# MCU.net
KiCad netlist of a schematic drawn in Altium Designer
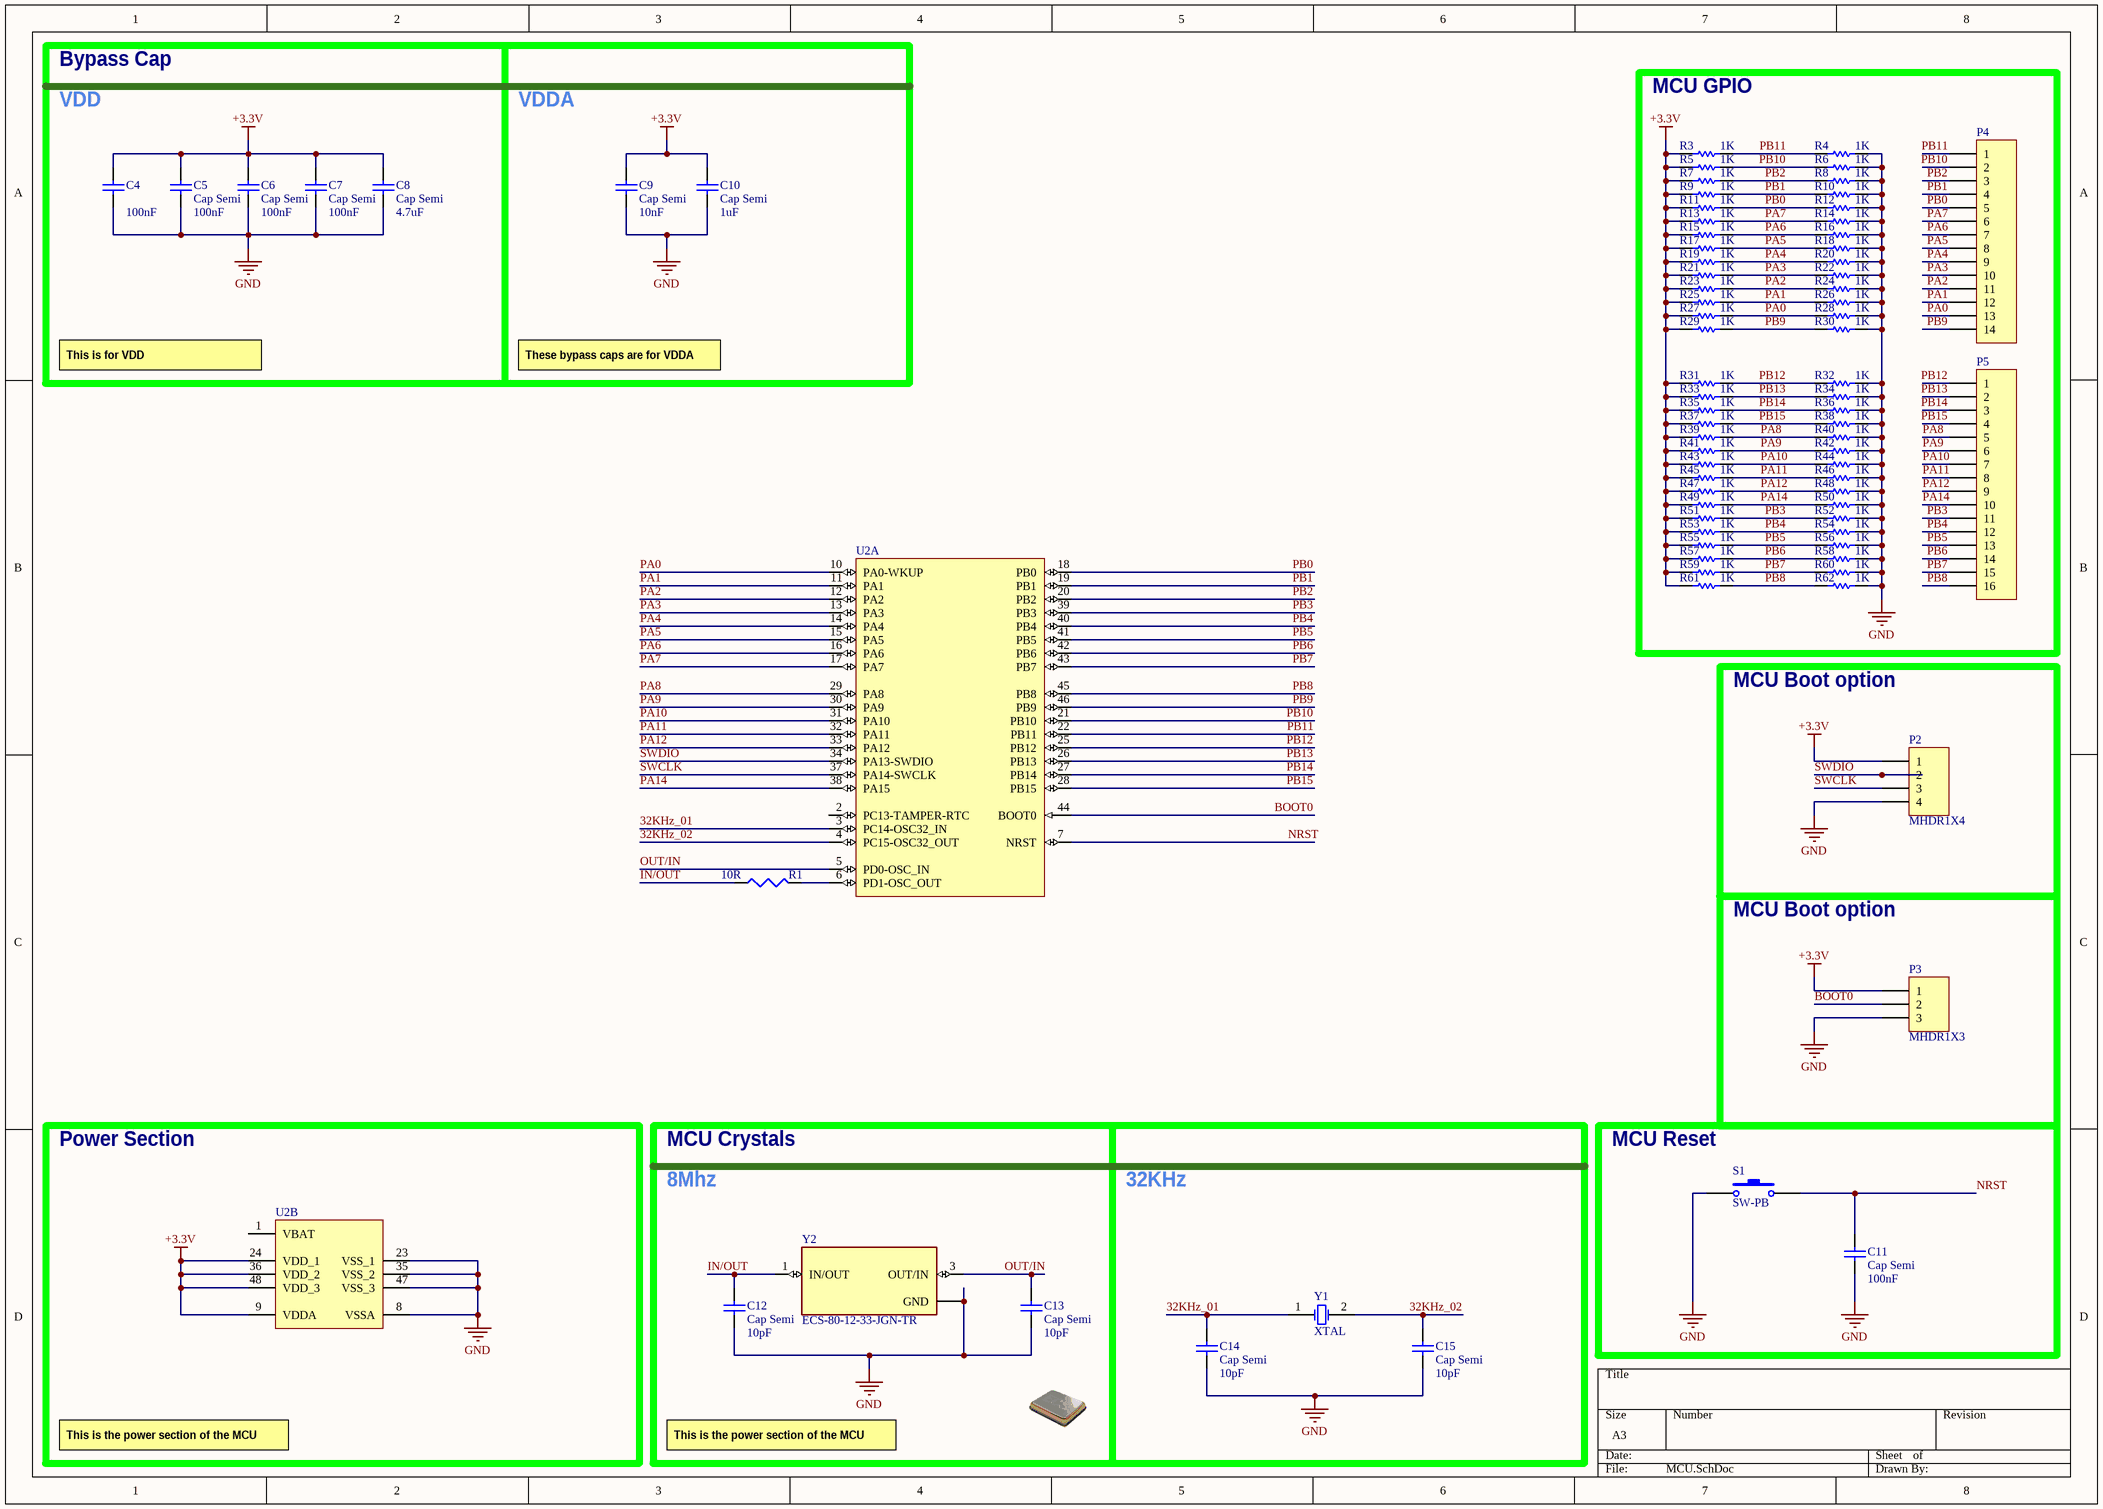
[diagram p0: MCU.SchDoc]

(export (version "E")
  (design (tool "Eeschema 10.0.6"))
  (components
    (comp (ref "C4")
      (value "100nF")
      (footprint "1608[0603]")
      (description "Capacitor (Semiconductor SIM Model)")
      (fields (field (name "PUBLISHER") "Altium Limited"))
      (libsource (lib "smartmcu") (part "Cap Semi"))
    )
    (comp (ref "C5")
      (value "Cap Semi")
      (footprint "1608[0603]")
      (description "Capacitor (Semiconductor SIM Model)")
      (fields (field (name "ALTIUM_VALUE") "100nF") (field (name "PUBLISHER") "Altium Limited"))
      (libsource (lib "Miscellaneous Devices") (part "Cap Semi"))
    )
    (comp (ref "C6")
      (value "Cap Semi")
      (footprint "1608[0603]")
      (description "Capacitor (Semiconductor SIM Model)")
      (fields (field (name "ALTIUM_VALUE") "100nF") (field (name "PUBLISHER") "Altium Limited"))
      (libsource (lib "Miscellaneous Devices") (part "Cap Semi"))
    )
    (comp (ref "C7")
      (value "Cap Semi")
      (footprint "1608[0603]")
      (description "Capacitor (Semiconductor SIM Model)")
      (fields (field (name "ALTIUM_VALUE") "100nF") (field (name "PUBLISHER") "Altium Limited"))
      (libsource (lib "Miscellaneous Devices") (part "Cap Semi"))
    )
    (comp (ref "C8")
      (value "Cap Semi")
      (footprint "1608[0603]")
      (description "Capacitor (Semiconductor SIM Model)")
      (fields (field (name "ALTIUM_VALUE") "4.7uF") (field (name "PUBLISHER") "Altium Limited"))
      (libsource (lib "Miscellaneous Devices") (part "Cap Semi"))
    )
    (comp (ref "C9")
      (value "Cap Semi")
      (footprint "1608[0603]")
      (description "Capacitor (Semiconductor SIM Model)")
      (fields (field (name "ALTIUM_VALUE") "10nF") (field (name "PUBLISHER") "Altium Limited"))
      (libsource (lib "Miscellaneous Devices") (part "Cap Semi"))
    )
    (comp (ref "C10")
      (value "Cap Semi")
      (footprint "1608[0603]")
      (description "Capacitor (Semiconductor SIM Model)")
      (fields (field (name "ALTIUM_VALUE") "1uF") (field (name "PUBLISHER") "Altium Limited"))
      (libsource (lib "Miscellaneous Devices") (part "Cap Semi"))
    )
    (comp (ref "C11")
      (value "Cap Semi")
      (footprint "1608[0603]")
      (description "Capacitor (Semiconductor SIM Model)")
      (fields (field (name "ALTIUM_VALUE") "100nF") (field (name "PUBLISHER") "Altium Limited"))
      (libsource (lib "Miscellaneous Devices") (part "Cap Semi"))
    )
    (comp (ref "C12")
      (value "Cap Semi")
      (footprint "0402")
      (description "Capacitor (Semiconductor SIM Model)")
      (fields (field (name "ALTIUM_VALUE") "10pF") (field (name "PUBLISHER") "Altium Limited"))
      (libsource (lib "Miscellaneous Devices") (part "Cap Semi"))
    )
    (comp (ref "C13")
      (value "Cap Semi")
      (footprint "0402")
      (description "Capacitor (Semiconductor SIM Model)")
      (fields (field (name "ALTIUM_VALUE") "10pF") (field (name "PUBLISHER") "Altium Limited"))
      (libsource (lib "Miscellaneous Devices") (part "Cap Semi"))
    )
    (comp (ref "C14")
      (value "Cap Semi")
      (footprint "0402")
      (description "Capacitor (Semiconductor SIM Model)")
      (fields (field (name "ALTIUM_VALUE") "10pF") (field (name "PUBLISHER") "Altium Limited"))
      (libsource (lib "Miscellaneous Devices") (part "Cap Semi"))
    )
    (comp (ref "C15")
      (value "Cap Semi")
      (footprint "0402")
      (description "Capacitor (Semiconductor SIM Model)")
      (fields (field (name "ALTIUM_VALUE") "10pF") (field (name "PUBLISHER") "Altium Limited"))
      (libsource (lib "Miscellaneous Devices") (part "Cap Semi"))
    )
    (comp (ref "P2")
      (value "MHDR1X4")
      (footprint "MHDR1X4")
      (description "Header, 4-Pin")
      (fields (field (name "PUBLISHER") "Altium Limited"))
      (libsource (lib "Miscellaneous Connectors") (part "MHDR1X4"))
    )
    (comp (ref "P3")
      (value "MHDR1X3")
      (footprint "MHDR1X3")
      (description "Header, 3-Pin")
      (fields (field (name "PUBLISHER") "Altium Limited"))
      (libsource (lib "Miscellaneous Connectors") (part "MHDR1X3"))
    )
    (comp (ref "P4")
      (value "Header 14")
      (footprint "MY_FE14")
      (description "Header, 14-Pin")
      (fields (field (name "ASID PART NUMBER") "Header 14-AS"))
      (libsource (lib "Mylib+Rev+4") (part "Header 14"))
    )
    (comp (ref "P5")
      (value "Header 16")
      (footprint "MY_FE16")
      (description "Header, 16-Pin")
      (fields (field (name "ASID PART NUMBER") "Header 16-AS"))
      (libsource (lib "Mylib+Rev+4") (part "Header 16"))
    )
    (comp (ref "R1")
      (value "10R")
      (footprint "J1-0603")
      (description "Resistor")
      (fields (field (name "Comment") "Res3") (field (name "PUBLISHER") "Altium Limited"))
      (libsource (lib "Miscellaneous Devices") (part "Res3"))
    )
    (comp (ref "R3")
      (value "1K")
      (footprint "MY_0603")
      (description "Standard resistor")
      (fields (field (name "ASID PART NUMBER") "Res-AS"))
      (libsource (lib "Mylib+Rev+4") (part "Res"))
    )
    (comp (ref "R4")
      (value "1K")
      (footprint "MY_0603")
      (description "Standard resistor")
      (fields (field (name "ASID PART NUMBER") "Res-AS"))
      (libsource (lib "Mylib+Rev+4") (part "Res"))
    )
    (comp (ref "R5")
      (value "1K")
      (footprint "MY_0603")
      (description "Standard resistor")
      (fields (field (name "ASID PART NUMBER") "Res-AS"))
      (libsource (lib "Mylib+Rev+4") (part "Res"))
    )
    (comp (ref "R6")
      (value "1K")
      (footprint "MY_0603")
      (description "Standard resistor")
      (fields (field (name "ASID PART NUMBER") "Res-AS"))
      (libsource (lib "Mylib+Rev+4") (part "Res"))
    )
    (comp (ref "R7")
      (value "1K")
      (footprint "MY_0603")
      (description "Standard resistor")
      (fields (field (name "ASID PART NUMBER") "Res-AS"))
      (libsource (lib "Mylib+Rev+4") (part "Res"))
    )
    (comp (ref "R8")
      (value "1K")
      (footprint "MY_0603")
      (description "Standard resistor")
      (fields (field (name "ASID PART NUMBER") "Res-AS"))
      (libsource (lib "Mylib+Rev+4") (part "Res"))
    )
    (comp (ref "R9")
      (value "1K")
      (footprint "MY_0603")
      (description "Standard resistor")
      (fields (field (name "ASID PART NUMBER") "Res-AS"))
      (libsource (lib "Mylib+Rev+4") (part "Res"))
    )
    (comp (ref "R10")
      (value "1K")
      (footprint "MY_0603")
      (description "Standard resistor")
      (fields (field (name "ASID PART NUMBER") "Res-AS"))
      (libsource (lib "Mylib+Rev+4") (part "Res"))
    )
    (comp (ref "R11")
      (value "1K")
      (footprint "MY_0603")
      (description "Standard resistor")
      (fields (field (name "ASID PART NUMBER") "Res-AS"))
      (libsource (lib "Mylib+Rev+4") (part "Res"))
    )
    (comp (ref "R12")
      (value "1K")
      (footprint "MY_0603")
      (description "Standard resistor")
      (fields (field (name "ASID PART NUMBER") "Res-AS"))
      (libsource (lib "Mylib+Rev+4") (part "Res"))
    )
    (comp (ref "R13")
      (value "1K")
      (footprint "MY_0603")
      (description "Standard resistor")
      (fields (field (name "ASID PART NUMBER") "Res-AS"))
      (libsource (lib "Mylib+Rev+4") (part "Res"))
    )
    (comp (ref "R14")
      (value "1K")
      (footprint "MY_0603")
      (description "Standard resistor")
      (fields (field (name "ASID PART NUMBER") "Res-AS"))
      (libsource (lib "Mylib+Rev+4") (part "Res"))
    )
    (comp (ref "R15")
      (value "1K")
      (footprint "MY_0603")
      (description "Standard resistor")
      (fields (field (name "ASID PART NUMBER") "Res-AS"))
      (libsource (lib "Mylib+Rev+4") (part "Res"))
    )
    (comp (ref "R16")
      (value "1K")
      (footprint "MY_0603")
      (description "Standard resistor")
      (fields (field (name "ASID PART NUMBER") "Res-AS"))
      (libsource (lib "Mylib+Rev+4") (part "Res"))
    )
    (comp (ref "R17")
      (value "1K")
      (footprint "MY_0603")
      (description "Standard resistor")
      (fields (field (name "ASID PART NUMBER") "Res-AS"))
      (libsource (lib "Mylib+Rev+4") (part "Res"))
    )
    (comp (ref "R18")
      (value "1K")
      (footprint "MY_0603")
      (description "Standard resistor")
      (fields (field (name "ASID PART NUMBER") "Res-AS"))
      (libsource (lib "Mylib+Rev+4") (part "Res"))
    )
    (comp (ref "R19")
      (value "1K")
      (footprint "MY_0603")
      (description "Standard resistor")
      (fields (field (name "ASID PART NUMBER") "Res-AS"))
      (libsource (lib "Mylib+Rev+4") (part "Res"))
    )
    (comp (ref "R20")
      (value "1K")
      (footprint "MY_0603")
      (description "Standard resistor")
      (fields (field (name "ASID PART NUMBER") "Res-AS"))
      (libsource (lib "Mylib+Rev+4") (part "Res"))
    )
    (comp (ref "R21")
      (value "1K")
      (footprint "MY_0603")
      (description "Standard resistor")
      (fields (field (name "ASID PART NUMBER") "Res-AS"))
      (libsource (lib "Mylib+Rev+4") (part "Res"))
    )
    (comp (ref "R22")
      (value "1K")
      (footprint "MY_0603")
      (description "Standard resistor")
      (fields (field (name "ASID PART NUMBER") "Res-AS"))
      (libsource (lib "Mylib+Rev+4") (part "Res"))
    )
    (comp (ref "R23")
      (value "1K")
      (footprint "MY_0603")
      (description "Standard resistor")
      (fields (field (name "ASID PART NUMBER") "Res-AS"))
      (libsource (lib "Mylib+Rev+4") (part "Res"))
    )
    (comp (ref "R24")
      (value "1K")
      (footprint "MY_0603")
      (description "Standard resistor")
      (fields (field (name "ASID PART NUMBER") "Res-AS"))
      (libsource (lib "Mylib+Rev+4") (part "Res"))
    )
    (comp (ref "R25")
      (value "1K")
      (footprint "MY_0603")
      (description "Standard resistor")
      (fields (field (name "ASID PART NUMBER") "Res-AS"))
      (libsource (lib "Mylib+Rev+4") (part "Res"))
    )
    (comp (ref "R26")
      (value "1K")
      (footprint "MY_0603")
      (description "Standard resistor")
      (fields (field (name "ASID PART NUMBER") "Res-AS"))
      (libsource (lib "Mylib+Rev+4") (part "Res"))
    )
    (comp (ref "R27")
      (value "1K")
      (footprint "MY_0603")
      (description "Standard resistor")
      (fields (field (name "ASID PART NUMBER") "Res-AS"))
      (libsource (lib "Mylib+Rev+4") (part "Res"))
    )
    (comp (ref "R28")
      (value "1K")
      (footprint "MY_0603")
      (description "Standard resistor")
      (fields (field (name "ASID PART NUMBER") "Res-AS"))
      (libsource (lib "Mylib+Rev+4") (part "Res"))
    )
    (comp (ref "R29")
      (value "1K")
      (footprint "MY_0603")
      (description "Standard resistor")
      (fields (field (name "ASID PART NUMBER") "Res-AS"))
      (libsource (lib "Mylib+Rev+4") (part "Res"))
    )
    (comp (ref "R30")
      (value "1K")
      (footprint "MY_0603")
      (description "Standard resistor")
      (fields (field (name "ASID PART NUMBER") "Res-AS"))
      (libsource (lib "Mylib+Rev+4") (part "Res"))
    )
    (comp (ref "R31")
      (value "1K")
      (footprint "MY_0603")
      (description "Standard resistor")
      (fields (field (name "ASID PART NUMBER") "Res-AS"))
      (libsource (lib "Mylib+Rev+4") (part "Res"))
    )
    (comp (ref "R32")
      (value "1K")
      (footprint "MY_0603")
      (description "Standard resistor")
      (fields (field (name "ASID PART NUMBER") "Res-AS"))
      (libsource (lib "Mylib+Rev+4") (part "Res"))
    )
    (comp (ref "R33")
      (value "1K")
      (footprint "MY_0603")
      (description "Standard resistor")
      (fields (field (name "ASID PART NUMBER") "Res-AS"))
      (libsource (lib "Mylib+Rev+4") (part "Res"))
    )
    (comp (ref "R34")
      (value "1K")
      (footprint "MY_0603")
      (description "Standard resistor")
      (fields (field (name "ASID PART NUMBER") "Res-AS"))
      (libsource (lib "Mylib+Rev+4") (part "Res"))
    )
    (comp (ref "R35")
      (value "1K")
      (footprint "MY_0603")
      (description "Standard resistor")
      (fields (field (name "ASID PART NUMBER") "Res-AS"))
      (libsource (lib "Mylib+Rev+4") (part "Res"))
    )
    (comp (ref "R36")
      (value "1K")
      (footprint "MY_0603")
      (description "Standard resistor")
      (fields (field (name "ASID PART NUMBER") "Res-AS"))
      (libsource (lib "Mylib+Rev+4") (part "Res"))
    )
    (comp (ref "R37")
      (value "1K")
      (footprint "MY_0603")
      (description "Standard resistor")
      (fields (field (name "ASID PART NUMBER") "Res-AS"))
      (libsource (lib "Mylib+Rev+4") (part "Res"))
    )
    (comp (ref "R38")
      (value "1K")
      (footprint "MY_0603")
      (description "Standard resistor")
      (fields (field (name "ASID PART NUMBER") "Res-AS"))
      (libsource (lib "Mylib+Rev+4") (part "Res"))
    )
    (comp (ref "R39")
      (value "1K")
      (footprint "MY_0603")
      (description "Standard resistor")
      (fields (field (name "ASID PART NUMBER") "Res-AS"))
      (libsource (lib "Mylib+Rev+4") (part "Res"))
    )
    (comp (ref "R40")
      (value "1K")
      (footprint "MY_0603")
      (description "Standard resistor")
      (fields (field (name "ASID PART NUMBER") "Res-AS"))
      (libsource (lib "Mylib+Rev+4") (part "Res"))
    )
    (comp (ref "R41")
      (value "1K")
      (footprint "MY_0603")
      (description "Standard resistor")
      (fields (field (name "ASID PART NUMBER") "Res-AS"))
      (libsource (lib "Mylib+Rev+4") (part "Res"))
    )
    (comp (ref "R42")
      (value "1K")
      (footprint "MY_0603")
      (description "Standard resistor")
      (fields (field (name "ASID PART NUMBER") "Res-AS"))
      (libsource (lib "Mylib+Rev+4") (part "Res"))
    )
    (comp (ref "R43")
      (value "1K")
      (footprint "MY_0603")
      (description "Standard resistor")
      (fields (field (name "ASID PART NUMBER") "Res-AS"))
      (libsource (lib "Mylib+Rev+4") (part "Res"))
    )
    (comp (ref "R44")
      (value "1K")
      (footprint "MY_0603")
      (description "Standard resistor")
      (fields (field (name "ASID PART NUMBER") "Res-AS"))
      (libsource (lib "Mylib+Rev+4") (part "Res"))
    )
    (comp (ref "R45")
      (value "1K")
      (footprint "MY_0603")
      (description "Standard resistor")
      (fields (field (name "ASID PART NUMBER") "Res-AS"))
      (libsource (lib "Mylib+Rev+4") (part "Res"))
    )
    (comp (ref "R46")
      (value "1K")
      (footprint "MY_0603")
      (description "Standard resistor")
      (fields (field (name "ASID PART NUMBER") "Res-AS"))
      (libsource (lib "Mylib+Rev+4") (part "Res"))
    )
    (comp (ref "R47")
      (value "1K")
      (footprint "MY_0603")
      (description "Standard resistor")
      (fields (field (name "ASID PART NUMBER") "Res-AS"))
      (libsource (lib "Mylib+Rev+4") (part "Res"))
    )
    (comp (ref "R48")
      (value "1K")
      (footprint "MY_0603")
      (description "Standard resistor")
      (fields (field (name "ASID PART NUMBER") "Res-AS"))
      (libsource (lib "Mylib+Rev+4") (part "Res"))
    )
    (comp (ref "R49")
      (value "1K")
      (footprint "MY_0603")
      (description "Standard resistor")
      (fields (field (name "ASID PART NUMBER") "Res-AS"))
      (libsource (lib "Mylib+Rev+4") (part "Res"))
    )
    (comp (ref "R50")
      (value "1K")
      (footprint "MY_0603")
      (description "Standard resistor")
      (fields (field (name "ASID PART NUMBER") "Res-AS"))
      (libsource (lib "Mylib+Rev+4") (part "Res"))
    )
    (comp (ref "R51")
      (value "1K")
      (footprint "MY_0603")
      (description "Standard resistor")
      (fields (field (name "ASID PART NUMBER") "Res-AS"))
      (libsource (lib "Mylib+Rev+4") (part "Res"))
    )
    (comp (ref "R52")
      (value "1K")
      (footprint "MY_0603")
      (description "Standard resistor")
      (fields (field (name "ASID PART NUMBER") "Res-AS"))
      (libsource (lib "Mylib+Rev+4") (part "Res"))
    )
    (comp (ref "R53")
      (value "1K")
      (footprint "MY_0603")
      (description "Standard resistor")
      (fields (field (name "ASID PART NUMBER") "Res-AS"))
      (libsource (lib "Mylib+Rev+4") (part "Res"))
    )
    (comp (ref "R54")
      (value "1K")
      (footprint "MY_0603")
      (description "Standard resistor")
      (fields (field (name "ASID PART NUMBER") "Res-AS"))
      (libsource (lib "Mylib+Rev+4") (part "Res"))
    )
    (comp (ref "R55")
      (value "1K")
      (footprint "MY_0603")
      (description "Standard resistor")
      (fields (field (name "ASID PART NUMBER") "Res-AS"))
      (libsource (lib "Mylib+Rev+4") (part "Res"))
    )
    (comp (ref "R56")
      (value "1K")
      (footprint "MY_0603")
      (description "Standard resistor")
      (fields (field (name "ASID PART NUMBER") "Res-AS"))
      (libsource (lib "Mylib+Rev+4") (part "Res"))
    )
    (comp (ref "R57")
      (value "1K")
      (footprint "MY_0603")
      (description "Standard resistor")
      (fields (field (name "ASID PART NUMBER") "Res-AS"))
      (libsource (lib "Mylib+Rev+4") (part "Res"))
    )
    (comp (ref "R58")
      (value "1K")
      (footprint "MY_0603")
      (description "Standard resistor")
      (fields (field (name "ASID PART NUMBER") "Res-AS"))
      (libsource (lib "Mylib+Rev+4") (part "Res"))
    )
    (comp (ref "R59")
      (value "1K")
      (footprint "MY_0603")
      (description "Standard resistor")
      (fields (field (name "ASID PART NUMBER") "Res-AS"))
      (libsource (lib "Mylib+Rev+4") (part "Res"))
    )
    (comp (ref "R60")
      (value "1K")
      (footprint "MY_0603")
      (description "Standard resistor")
      (fields (field (name "ASID PART NUMBER") "Res-AS"))
      (libsource (lib "Mylib+Rev+4") (part "Res"))
    )
    (comp (ref "R61")
      (value "1K")
      (footprint "MY_0603")
      (description "Standard resistor")
      (fields (field (name "ASID PART NUMBER") "Res-AS"))
      (libsource (lib "Mylib+Rev+4") (part "Res"))
    )
    (comp (ref "R62")
      (value "1K")
      (footprint "MY_0603")
      (description "Standard resistor")
      (fields (field (name "ASID PART NUMBER") "Res-AS"))
      (libsource (lib "Mylib+Rev+4") (part "Res"))
    )
    (comp (ref "S1")
      (value "SW-PB")
      (footprint "SPST-2")
      (description "Switch")
      (fields (field (name "PUBLISHER") "Altium Limited"))
      (libsource (lib "Miscellaneous Devices") (part "SW-PB"))
    )
    (comp (ref "U2")
      (value "~")
      (footprint "STM-LQFP48_N")
      (fields (field (name "PARTNUMBER") "STM32F103C8T6"))
      (libsource (lib "smartmcu") (part "STM32F103C8T6"))
    )
    (comp (ref "Y1")
      (value "XTAL")
      (footprint "R38")
      (description "Crystal Oscillator")
      (fields (field (name "PUBLISHER") "Altium Limited"))
      (libsource (lib "Miscellaneous Devices") (part "XTAL"))
    )
    (comp (ref "Y2")
      (value "ECS-80-12-33-JGN-TR")
      (footprint "XTAL_ECS-240-8-33-AGN-TR")
      (description "8MHz Â±20ppm Crystal 12pF 400 Ohms 4-SMD, No Lead")
      (fields
        (field (name "MF") "ECS Inc.")
        (field (name "BUYPART") "https://www.snapeda.com/parts/ECS-80-12-33-JGN-TR/ECS%20Inc./view-part/4477300/?ref=eda")
      )
      (libsource (lib "ECS-80-12-33-JGN-TR") (part "ECS-80-12-33-JGN-TR"))
    )
  )
  (nets
    (net (code "1") (name "+3.3V") (class "Default")
      (node (ref "C10") (pin "2") (pinfunction "2_2") (pintype "passive"))
      (node (ref "C4") (pin "2") (pinfunction "2_2") (pintype "passive"))
      (node (ref "C5") (pin "2") (pinfunction "2_2") (pintype "passive"))
      (node (ref "C6") (pin "2") (pinfunction "2_2") (pintype "passive"))
      (node (ref "C7") (pin "2") (pinfunction "2_2") (pintype "passive"))
      (node (ref "C8") (pin "2") (pinfunction "2_2") (pintype "passive"))
      (node (ref "C9") (pin "2") (pinfunction "2_2") (pintype "passive"))
      (node (ref "P2") (pin "1") (pinfunction "1_1") (pintype "passive"))
      (node (ref "P3") (pin "1") (pinfunction "1_1") (pintype "passive"))
      (node (ref "R11") (pin "1") (pinfunction "1_1") (pintype "passive"))
      (node (ref "R13") (pin "1") (pinfunction "1_1") (pintype "passive"))
      (node (ref "R15") (pin "1") (pinfunction "1_1") (pintype "passive"))
      (node (ref "R17") (pin "1") (pinfunction "1_1") (pintype "passive"))
      (node (ref "R19") (pin "1") (pinfunction "1_1") (pintype "passive"))
      (node (ref "R21") (pin "1") (pinfunction "1_1") (pintype "passive"))
      (node (ref "R23") (pin "1") (pinfunction "1_1") (pintype "passive"))
      (node (ref "R25") (pin "1") (pinfunction "1_1") (pintype "passive"))
      (node (ref "R27") (pin "1") (pinfunction "1_1") (pintype "passive"))
      (node (ref "R29") (pin "1") (pinfunction "1_1") (pintype "passive"))
      (node (ref "R3") (pin "1") (pinfunction "1_1") (pintype "passive"))
      (node (ref "R31") (pin "1") (pinfunction "1_1") (pintype "passive"))
      (node (ref "R33") (pin "1") (pinfunction "1_1") (pintype "passive"))
      (node (ref "R35") (pin "1") (pinfunction "1_1") (pintype "passive"))
      (node (ref "R37") (pin "1") (pinfunction "1_1") (pintype "passive"))
      (node (ref "R39") (pin "1") (pinfunction "1_1") (pintype "passive"))
      (node (ref "R41") (pin "1") (pinfunction "1_1") (pintype "passive"))
      (node (ref "R43") (pin "1") (pinfunction "1_1") (pintype "passive"))
      (node (ref "R45") (pin "1") (pinfunction "1_1") (pintype "passive"))
      (node (ref "R47") (pin "1") (pinfunction "1_1") (pintype "passive"))
      (node (ref "R49") (pin "1") (pinfunction "1_1") (pintype "passive"))
      (node (ref "R5") (pin "1") (pinfunction "1_1") (pintype "passive"))
      (node (ref "R51") (pin "1") (pinfunction "1_1") (pintype "passive"))
      (node (ref "R53") (pin "1") (pinfunction "1_1") (pintype "passive"))
      (node (ref "R55") (pin "1") (pinfunction "1_1") (pintype "passive"))
      (node (ref "R57") (pin "1") (pinfunction "1_1") (pintype "passive"))
      (node (ref "R59") (pin "1") (pinfunction "1_1") (pintype "passive"))
      (node (ref "R61") (pin "1") (pinfunction "1_1") (pintype "passive"))
      (node (ref "R7") (pin "1") (pinfunction "1_1") (pintype "passive"))
      (node (ref "R9") (pin "1") (pinfunction "1_1") (pintype "passive"))
      (node (ref "U2") (pin "24") (pinfunction "VDD_1_24") (pintype "power_in"))
      (node (ref "U2") (pin "36") (pinfunction "VDD_2_36") (pintype "power_in"))
      (node (ref "U2") (pin "48") (pinfunction "VDD_3_48") (pintype "power_in"))
      (node (ref "U2") (pin "9") (pinfunction "VDDA_9") (pintype "power_in"))
    )
    (net (code "2") (name "/32KHz_01") (class "Default")
      (node (ref "C14") (pin "2") (pinfunction "2_2") (pintype "passive"))
      (node (ref "U2") (pin "3") (pinfunction "PC14-OSC32_IN_3") (pintype "bidirectional"))
      (node (ref "Y1") (pin "1") (pinfunction "OSC1_1") (pintype "passive"))
    )
    (net (code "3") (name "/32KHz_02") (class "Default")
      (node (ref "C15") (pin "2") (pinfunction "2_2") (pintype "passive"))
      (node (ref "U2") (pin "4") (pinfunction "PC15-OSC32_OUT_4") (pintype "bidirectional"))
      (node (ref "Y1") (pin "2") (pinfunction "OSC2_2") (pintype "passive"))
    )
    (net (code "4") (name "/BOOT0") (class "Default")
      (node (ref "P3") (pin "2") (pinfunction "2_2") (pintype "passive"))
      (node (ref "U2") (pin "44") (pinfunction "BOOT0_44") (pintype "input"))
    )
    (net (code "5") (name "/IN{slash}OUT") (class "Default")
      (node (ref "C12") (pin "2") (pinfunction "2_2") (pintype "passive"))
      (node (ref "R1") (pin "1") (pinfunction "1_1") (pintype "passive"))
      (node (ref "Y2") (pin "1") (pinfunction "IN/OUT_1") (pintype "bidirectional"))
    )
    (net (code "6") (name "/NRST") (class "Default")
      (node (ref "C11") (pin "2") (pinfunction "2_2") (pintype "passive"))
      (node (ref "S1") (pin "2") (pinfunction "2_2") (pintype "passive"))
      (node (ref "U2") (pin "7") (pinfunction "NRST_7") (pintype "bidirectional"))
    )
    (net (code "7") (name "/OUT{slash}IN") (class "Default")
      (node (ref "C13") (pin "2") (pinfunction "2_2") (pintype "passive"))
      (node (ref "U2") (pin "5") (pinfunction "PD0-OSC_IN_5") (pintype "bidirectional"))
      (node (ref "Y2") (pin "3") (pinfunction "OUT/IN_3") (pintype "bidirectional"))
    )
    (net (code "8") (name "/PA0") (class "Default")
      (node (ref "P4") (pin "13") (pinfunction "13_13") (pintype "passive"))
      (node (ref "R27") (pin "2") (pinfunction "2_2") (pintype "passive"))
      (node (ref "R28") (pin "1") (pinfunction "1_1") (pintype "passive"))
      (node (ref "U2") (pin "10") (pinfunction "PA0-WKUP_10") (pintype "bidirectional"))
    )
    (net (code "9") (name "/PA1") (class "Default")
      (node (ref "P4") (pin "12") (pinfunction "12_12") (pintype "passive"))
      (node (ref "R25") (pin "2") (pinfunction "2_2") (pintype "passive"))
      (node (ref "R26") (pin "1") (pinfunction "1_1") (pintype "passive"))
      (node (ref "U2") (pin "11") (pinfunction "PA1_11") (pintype "bidirectional"))
    )
    (net (code "10") (name "/PA2") (class "Default")
      (node (ref "P4") (pin "11") (pinfunction "11_11") (pintype "passive"))
      (node (ref "R23") (pin "2") (pinfunction "2_2") (pintype "passive"))
      (node (ref "R24") (pin "1") (pinfunction "1_1") (pintype "passive"))
      (node (ref "U2") (pin "12") (pinfunction "PA2_12") (pintype "bidirectional"))
    )
    (net (code "11") (name "/PA3") (class "Default")
      (node (ref "P4") (pin "10") (pinfunction "10_10") (pintype "passive"))
      (node (ref "R21") (pin "2") (pinfunction "2_2") (pintype "passive"))
      (node (ref "R22") (pin "1") (pinfunction "1_1") (pintype "passive"))
      (node (ref "U2") (pin "13") (pinfunction "PA3_13") (pintype "bidirectional"))
    )
    (net (code "12") (name "/PA4") (class "Default")
      (node (ref "P4") (pin "9") (pinfunction "9_9") (pintype "passive"))
      (node (ref "R19") (pin "2") (pinfunction "2_2") (pintype "passive"))
      (node (ref "R20") (pin "1") (pinfunction "1_1") (pintype "passive"))
      (node (ref "U2") (pin "14") (pinfunction "PA4_14") (pintype "bidirectional"))
    )
    (net (code "13") (name "/PA5") (class "Default")
      (node (ref "P4") (pin "8") (pinfunction "8_8") (pintype "passive"))
      (node (ref "R17") (pin "2") (pinfunction "2_2") (pintype "passive"))
      (node (ref "R18") (pin "1") (pinfunction "1_1") (pintype "passive"))
      (node (ref "U2") (pin "15") (pinfunction "PA5_15") (pintype "bidirectional"))
    )
    (net (code "14") (name "/PA6") (class "Default")
      (node (ref "P4") (pin "7") (pinfunction "7_7") (pintype "passive"))
      (node (ref "R15") (pin "2") (pinfunction "2_2") (pintype "passive"))
      (node (ref "R16") (pin "1") (pinfunction "1_1") (pintype "passive"))
      (node (ref "U2") (pin "16") (pinfunction "PA6_16") (pintype "bidirectional"))
    )
    (net (code "15") (name "/PA7") (class "Default")
      (node (ref "P4") (pin "6") (pinfunction "6_6") (pintype "passive"))
      (node (ref "R13") (pin "2") (pinfunction "2_2") (pintype "passive"))
      (node (ref "R14") (pin "1") (pinfunction "1_1") (pintype "passive"))
      (node (ref "U2") (pin "17") (pinfunction "PA7_17") (pintype "bidirectional"))
    )
    (net (code "16") (name "/PA8") (class "Default")
      (node (ref "P5") (pin "5") (pinfunction "5_5") (pintype "passive"))
      (node (ref "R39") (pin "2") (pinfunction "2_2") (pintype "passive"))
      (node (ref "R40") (pin "1") (pinfunction "1_1") (pintype "passive"))
      (node (ref "U2") (pin "29") (pinfunction "PA8_29") (pintype "bidirectional"))
    )
    (net (code "17") (name "/PA9") (class "Default")
      (node (ref "P5") (pin "6") (pinfunction "6_6") (pintype "passive"))
      (node (ref "R41") (pin "2") (pinfunction "2_2") (pintype "passive"))
      (node (ref "R42") (pin "1") (pinfunction "1_1") (pintype "passive"))
      (node (ref "U2") (pin "30") (pinfunction "PA9_30") (pintype "bidirectional"))
    )
    (net (code "18") (name "/PA10") (class "Default")
      (node (ref "P5") (pin "7") (pinfunction "7_7") (pintype "passive"))
      (node (ref "R43") (pin "2") (pinfunction "2_2") (pintype "passive"))
      (node (ref "R44") (pin "1") (pinfunction "1_1") (pintype "passive"))
      (node (ref "U2") (pin "31") (pinfunction "PA10_31") (pintype "bidirectional"))
    )
    (net (code "19") (name "/PA11") (class "Default")
      (node (ref "P5") (pin "8") (pinfunction "8_8") (pintype "passive"))
      (node (ref "R45") (pin "2") (pinfunction "2_2") (pintype "passive"))
      (node (ref "R46") (pin "1") (pinfunction "1_1") (pintype "passive"))
      (node (ref "U2") (pin "32") (pinfunction "PA11_32") (pintype "bidirectional"))
    )
    (net (code "20") (name "/PA12") (class "Default")
      (node (ref "P5") (pin "9") (pinfunction "9_9") (pintype "passive"))
      (node (ref "R47") (pin "2") (pinfunction "2_2") (pintype "passive"))
      (node (ref "R48") (pin "1") (pinfunction "1_1") (pintype "passive"))
      (node (ref "U2") (pin "33") (pinfunction "PA12_33") (pintype "bidirectional"))
    )
    (net (code "21") (name "/PA14") (class "Default")
      (node (ref "P5") (pin "10") (pinfunction "10_10") (pintype "passive"))
      (node (ref "R49") (pin "2") (pinfunction "2_2") (pintype "passive"))
      (node (ref "R50") (pin "1") (pinfunction "1_1") (pintype "passive"))
      (node (ref "U2") (pin "38") (pinfunction "PA15_38") (pintype "bidirectional"))
    )
    (net (code "22") (name "/PB0") (class "Default")
      (node (ref "P4") (pin "5") (pinfunction "5_5") (pintype "passive"))
      (node (ref "R11") (pin "2") (pinfunction "2_2") (pintype "passive"))
      (node (ref "R12") (pin "1") (pinfunction "1_1") (pintype "passive"))
      (node (ref "U2") (pin "18") (pinfunction "PB0_18") (pintype "bidirectional"))
    )
    (net (code "23") (name "/PB1") (class "Default")
      (node (ref "P4") (pin "4") (pinfunction "4_4") (pintype "passive"))
      (node (ref "R10") (pin "1") (pinfunction "1_1") (pintype "passive"))
      (node (ref "R9") (pin "2") (pinfunction "2_2") (pintype "passive"))
      (node (ref "U2") (pin "19") (pinfunction "PB1_19") (pintype "bidirectional"))
    )
    (net (code "24") (name "/PB2") (class "Default")
      (node (ref "P4") (pin "3") (pinfunction "3_3") (pintype "passive"))
      (node (ref "R7") (pin "2") (pinfunction "2_2") (pintype "passive"))
      (node (ref "R8") (pin "1") (pinfunction "1_1") (pintype "passive"))
      (node (ref "U2") (pin "20") (pinfunction "PB2_20") (pintype "bidirectional"))
    )
    (net (code "25") (name "/PB3") (class "Default")
      (node (ref "P5") (pin "11") (pinfunction "11_11") (pintype "passive"))
      (node (ref "R51") (pin "2") (pinfunction "2_2") (pintype "passive"))
      (node (ref "R52") (pin "1") (pinfunction "1_1") (pintype "passive"))
      (node (ref "U2") (pin "39") (pinfunction "PB3_39") (pintype "bidirectional"))
    )
    (net (code "26") (name "/PB4") (class "Default")
      (node (ref "P5") (pin "12") (pinfunction "12_12") (pintype "passive"))
      (node (ref "R53") (pin "2") (pinfunction "2_2") (pintype "passive"))
      (node (ref "R54") (pin "1") (pinfunction "1_1") (pintype "passive"))
      (node (ref "U2") (pin "40") (pinfunction "PB4_40") (pintype "bidirectional"))
    )
    (net (code "27") (name "/PB5") (class "Default")
      (node (ref "P5") (pin "13") (pinfunction "13_13") (pintype "passive"))
      (node (ref "R55") (pin "2") (pinfunction "2_2") (pintype "passive"))
      (node (ref "R56") (pin "1") (pinfunction "1_1") (pintype "passive"))
      (node (ref "U2") (pin "41") (pinfunction "PB5_41") (pintype "bidirectional"))
    )
    (net (code "28") (name "/PB6") (class "Default")
      (node (ref "P5") (pin "14") (pinfunction "14_14") (pintype "passive"))
      (node (ref "R57") (pin "2") (pinfunction "2_2") (pintype "passive"))
      (node (ref "R58") (pin "1") (pinfunction "1_1") (pintype "passive"))
      (node (ref "U2") (pin "42") (pinfunction "PB6_42") (pintype "bidirectional"))
    )
    (net (code "29") (name "/PB7") (class "Default")
      (node (ref "P5") (pin "15") (pinfunction "15_15") (pintype "passive"))
      (node (ref "R59") (pin "2") (pinfunction "2_2") (pintype "passive"))
      (node (ref "R60") (pin "1") (pinfunction "1_1") (pintype "passive"))
      (node (ref "U2") (pin "43") (pinfunction "PB7_43") (pintype "bidirectional"))
    )
    (net (code "30") (name "/PB8") (class "Default")
      (node (ref "P5") (pin "16") (pinfunction "16_16") (pintype "passive"))
      (node (ref "R61") (pin "2") (pinfunction "2_2") (pintype "passive"))
      (node (ref "R62") (pin "1") (pinfunction "1_1") (pintype "passive"))
      (node (ref "U2") (pin "45") (pinfunction "PB8_45") (pintype "bidirectional"))
    )
    (net (code "31") (name "/PB9") (class "Default")
      (node (ref "P4") (pin "14") (pinfunction "14_14") (pintype "passive"))
      (node (ref "R29") (pin "2") (pinfunction "2_2") (pintype "passive"))
      (node (ref "R30") (pin "1") (pinfunction "1_1") (pintype "passive"))
      (node (ref "U2") (pin "46") (pinfunction "PB9_46") (pintype "bidirectional"))
    )
    (net (code "32") (name "/PB10") (class "Default")
      (node (ref "P4") (pin "2") (pinfunction "2_2") (pintype "passive"))
      (node (ref "R5") (pin "2") (pinfunction "2_2") (pintype "passive"))
      (node (ref "R6") (pin "1") (pinfunction "1_1") (pintype "passive"))
      (node (ref "U2") (pin "21") (pinfunction "PB10_21") (pintype "bidirectional"))
    )
    (net (code "33") (name "/PB11") (class "Default")
      (node (ref "P4") (pin "1") (pinfunction "1_1") (pintype "passive"))
      (node (ref "R3") (pin "2") (pinfunction "2_2") (pintype "passive"))
      (node (ref "R4") (pin "1") (pinfunction "1_1") (pintype "passive"))
      (node (ref "U2") (pin "22") (pinfunction "PB11_22") (pintype "bidirectional"))
    )
    (net (code "34") (name "/PB12") (class "Default")
      (node (ref "P5") (pin "1") (pinfunction "1_1") (pintype "passive"))
      (node (ref "R31") (pin "2") (pinfunction "2_2") (pintype "passive"))
      (node (ref "R32") (pin "1") (pinfunction "1_1") (pintype "passive"))
      (node (ref "U2") (pin "25") (pinfunction "PB12_25") (pintype "bidirectional"))
    )
    (net (code "35") (name "/PB13") (class "Default")
      (node (ref "P5") (pin "2") (pinfunction "2_2") (pintype "passive"))
      (node (ref "R33") (pin "2") (pinfunction "2_2") (pintype "passive"))
      (node (ref "R34") (pin "1") (pinfunction "1_1") (pintype "passive"))
      (node (ref "U2") (pin "26") (pinfunction "PB13_26") (pintype "bidirectional"))
    )
    (net (code "36") (name "/PB14") (class "Default")
      (node (ref "P5") (pin "3") (pinfunction "3_3") (pintype "passive"))
      (node (ref "R35") (pin "2") (pinfunction "2_2") (pintype "passive"))
      (node (ref "R36") (pin "1") (pinfunction "1_1") (pintype "passive"))
      (node (ref "U2") (pin "27") (pinfunction "PB14_27") (pintype "bidirectional"))
    )
    (net (code "37") (name "/PB15") (class "Default")
      (node (ref "P5") (pin "4") (pinfunction "4_4") (pintype "passive"))
      (node (ref "R37") (pin "2") (pinfunction "2_2") (pintype "passive"))
      (node (ref "R38") (pin "1") (pinfunction "1_1") (pintype "passive"))
      (node (ref "U2") (pin "28") (pinfunction "PB15_28") (pintype "bidirectional"))
    )
    (net (code "38") (name "/SWCLK") (class "Default")
      (node (ref "P2") (pin "3") (pinfunction "3_3") (pintype "passive"))
      (node (ref "U2") (pin "37") (pinfunction "PA14-SWCLK_37") (pintype "bidirectional"))
    )
    (net (code "39") (name "/SWDIO") (class "Default")
      (node (ref "P2") (pin "2") (pinfunction "2_2") (pintype "passive"))
      (node (ref "U2") (pin "34") (pinfunction "PA13-SWDIO_34") (pintype "bidirectional"))
    )
    (net (code "40") (name "GND") (class "Default")
      (node (ref "C10") (pin "1") (pinfunction "1_1") (pintype "passive"))
      (node (ref "C11") (pin "1") (pinfunction "1_1") (pintype "passive"))
      (node (ref "C12") (pin "1") (pinfunction "1_1") (pintype "passive"))
      (node (ref "C13") (pin "1") (pinfunction "1_1") (pintype "passive"))
      (node (ref "C14") (pin "1") (pinfunction "1_1") (pintype "passive"))
      (node (ref "C15") (pin "1") (pinfunction "1_1") (pintype "passive"))
      (node (ref "C4") (pin "1") (pinfunction "1_1") (pintype "passive"))
      (node (ref "C5") (pin "1") (pinfunction "1_1") (pintype "passive"))
      (node (ref "C6") (pin "1") (pinfunction "1_1") (pintype "passive"))
      (node (ref "C7") (pin "1") (pinfunction "1_1") (pintype "passive"))
      (node (ref "C8") (pin "1") (pinfunction "1_1") (pintype "passive"))
      (node (ref "C9") (pin "1") (pinfunction "1_1") (pintype "passive"))
      (node (ref "P2") (pin "4") (pinfunction "4_4") (pintype "passive"))
      (node (ref "P3") (pin "3") (pinfunction "3_3") (pintype "passive"))
      (node (ref "R10") (pin "2") (pinfunction "2_2") (pintype "passive"))
      (node (ref "R12") (pin "2") (pinfunction "2_2") (pintype "passive"))
      (node (ref "R14") (pin "2") (pinfunction "2_2") (pintype "passive"))
      (node (ref "R16") (pin "2") (pinfunction "2_2") (pintype "passive"))
      (node (ref "R18") (pin "2") (pinfunction "2_2") (pintype "passive"))
      (node (ref "R20") (pin "2") (pinfunction "2_2") (pintype "passive"))
      (node (ref "R22") (pin "2") (pinfunction "2_2") (pintype "passive"))
      (node (ref "R24") (pin "2") (pinfunction "2_2") (pintype "passive"))
      (node (ref "R26") (pin "2") (pinfunction "2_2") (pintype "passive"))
      (node (ref "R28") (pin "2") (pinfunction "2_2") (pintype "passive"))
      (node (ref "R30") (pin "2") (pinfunction "2_2") (pintype "passive"))
      (node (ref "R32") (pin "2") (pinfunction "2_2") (pintype "passive"))
      (node (ref "R34") (pin "2") (pinfunction "2_2") (pintype "passive"))
      (node (ref "R36") (pin "2") (pinfunction "2_2") (pintype "passive"))
      (node (ref "R38") (pin "2") (pinfunction "2_2") (pintype "passive"))
      (node (ref "R4") (pin "2") (pinfunction "2_2") (pintype "passive"))
      (node (ref "R40") (pin "2") (pinfunction "2_2") (pintype "passive"))
      (node (ref "R42") (pin "2") (pinfunction "2_2") (pintype "passive"))
      (node (ref "R44") (pin "2") (pinfunction "2_2") (pintype "passive"))
      (node (ref "R46") (pin "2") (pinfunction "2_2") (pintype "passive"))
      (node (ref "R48") (pin "2") (pinfunction "2_2") (pintype "passive"))
      (node (ref "R50") (pin "2") (pinfunction "2_2") (pintype "passive"))
      (node (ref "R52") (pin "2") (pinfunction "2_2") (pintype "passive"))
      (node (ref "R54") (pin "2") (pinfunction "2_2") (pintype "passive"))
      (node (ref "R56") (pin "2") (pinfunction "2_2") (pintype "passive"))
      (node (ref "R58") (pin "2") (pinfunction "2_2") (pintype "passive"))
      (node (ref "R6") (pin "2") (pinfunction "2_2") (pintype "passive"))
      (node (ref "R60") (pin "2") (pinfunction "2_2") (pintype "passive"))
      (node (ref "R62") (pin "2") (pinfunction "2_2") (pintype "passive"))
      (node (ref "R8") (pin "2") (pinfunction "2_2") (pintype "passive"))
      (node (ref "S1") (pin "1") (pinfunction "1_1") (pintype "passive"))
      (node (ref "U2") (pin "23") (pinfunction "VSS_1_23") (pintype "power_in"))
      (node (ref "U2") (pin "35") (pinfunction "VSS_2_35") (pintype "power_in"))
      (node (ref "U2") (pin "47") (pinfunction "VSS_3_47") (pintype "power_in"))
      (node (ref "U2") (pin "8") (pinfunction "VSSA_8") (pintype "power_in"))
      (node (ref "Y2") (pin "2") (pinfunction "GND_2") (pintype "power_in"))
      (node (ref "Y2") (pin "4") (pinfunction "GND_4") (pintype "power_in"))
    )
    (net (code "41") (name "Net-(U2A-PD1-OSC_OUT)") (class "Default")
      (node (ref "R1") (pin "2") (pinfunction "2_2") (pintype "passive"))
      (node (ref "U2") (pin "6") (pinfunction "PD1-OSC_OUT_6") (pintype "bidirectional"))
    )
    (net (code "42") (name "unconnected-(U2A-PC13-TAMPER-RTC-Pad2)") (class "Default")
      (node (ref "U2") (pin "2") (pinfunction "PC13-TAMPER-RTC_2") (pintype "bidirectional"))
    )
    (net (code "43") (name "unconnected-(U2B-VBAT-Pad1)") (class "Default")
      (node (ref "U2") (pin "1") (pinfunction "VBAT_1") (pintype "power_in"))
    )
  )
)
